# MPBoard_L3_Relay2_ext.net
KiCad netlist of a schematic drawn in Altium Designer
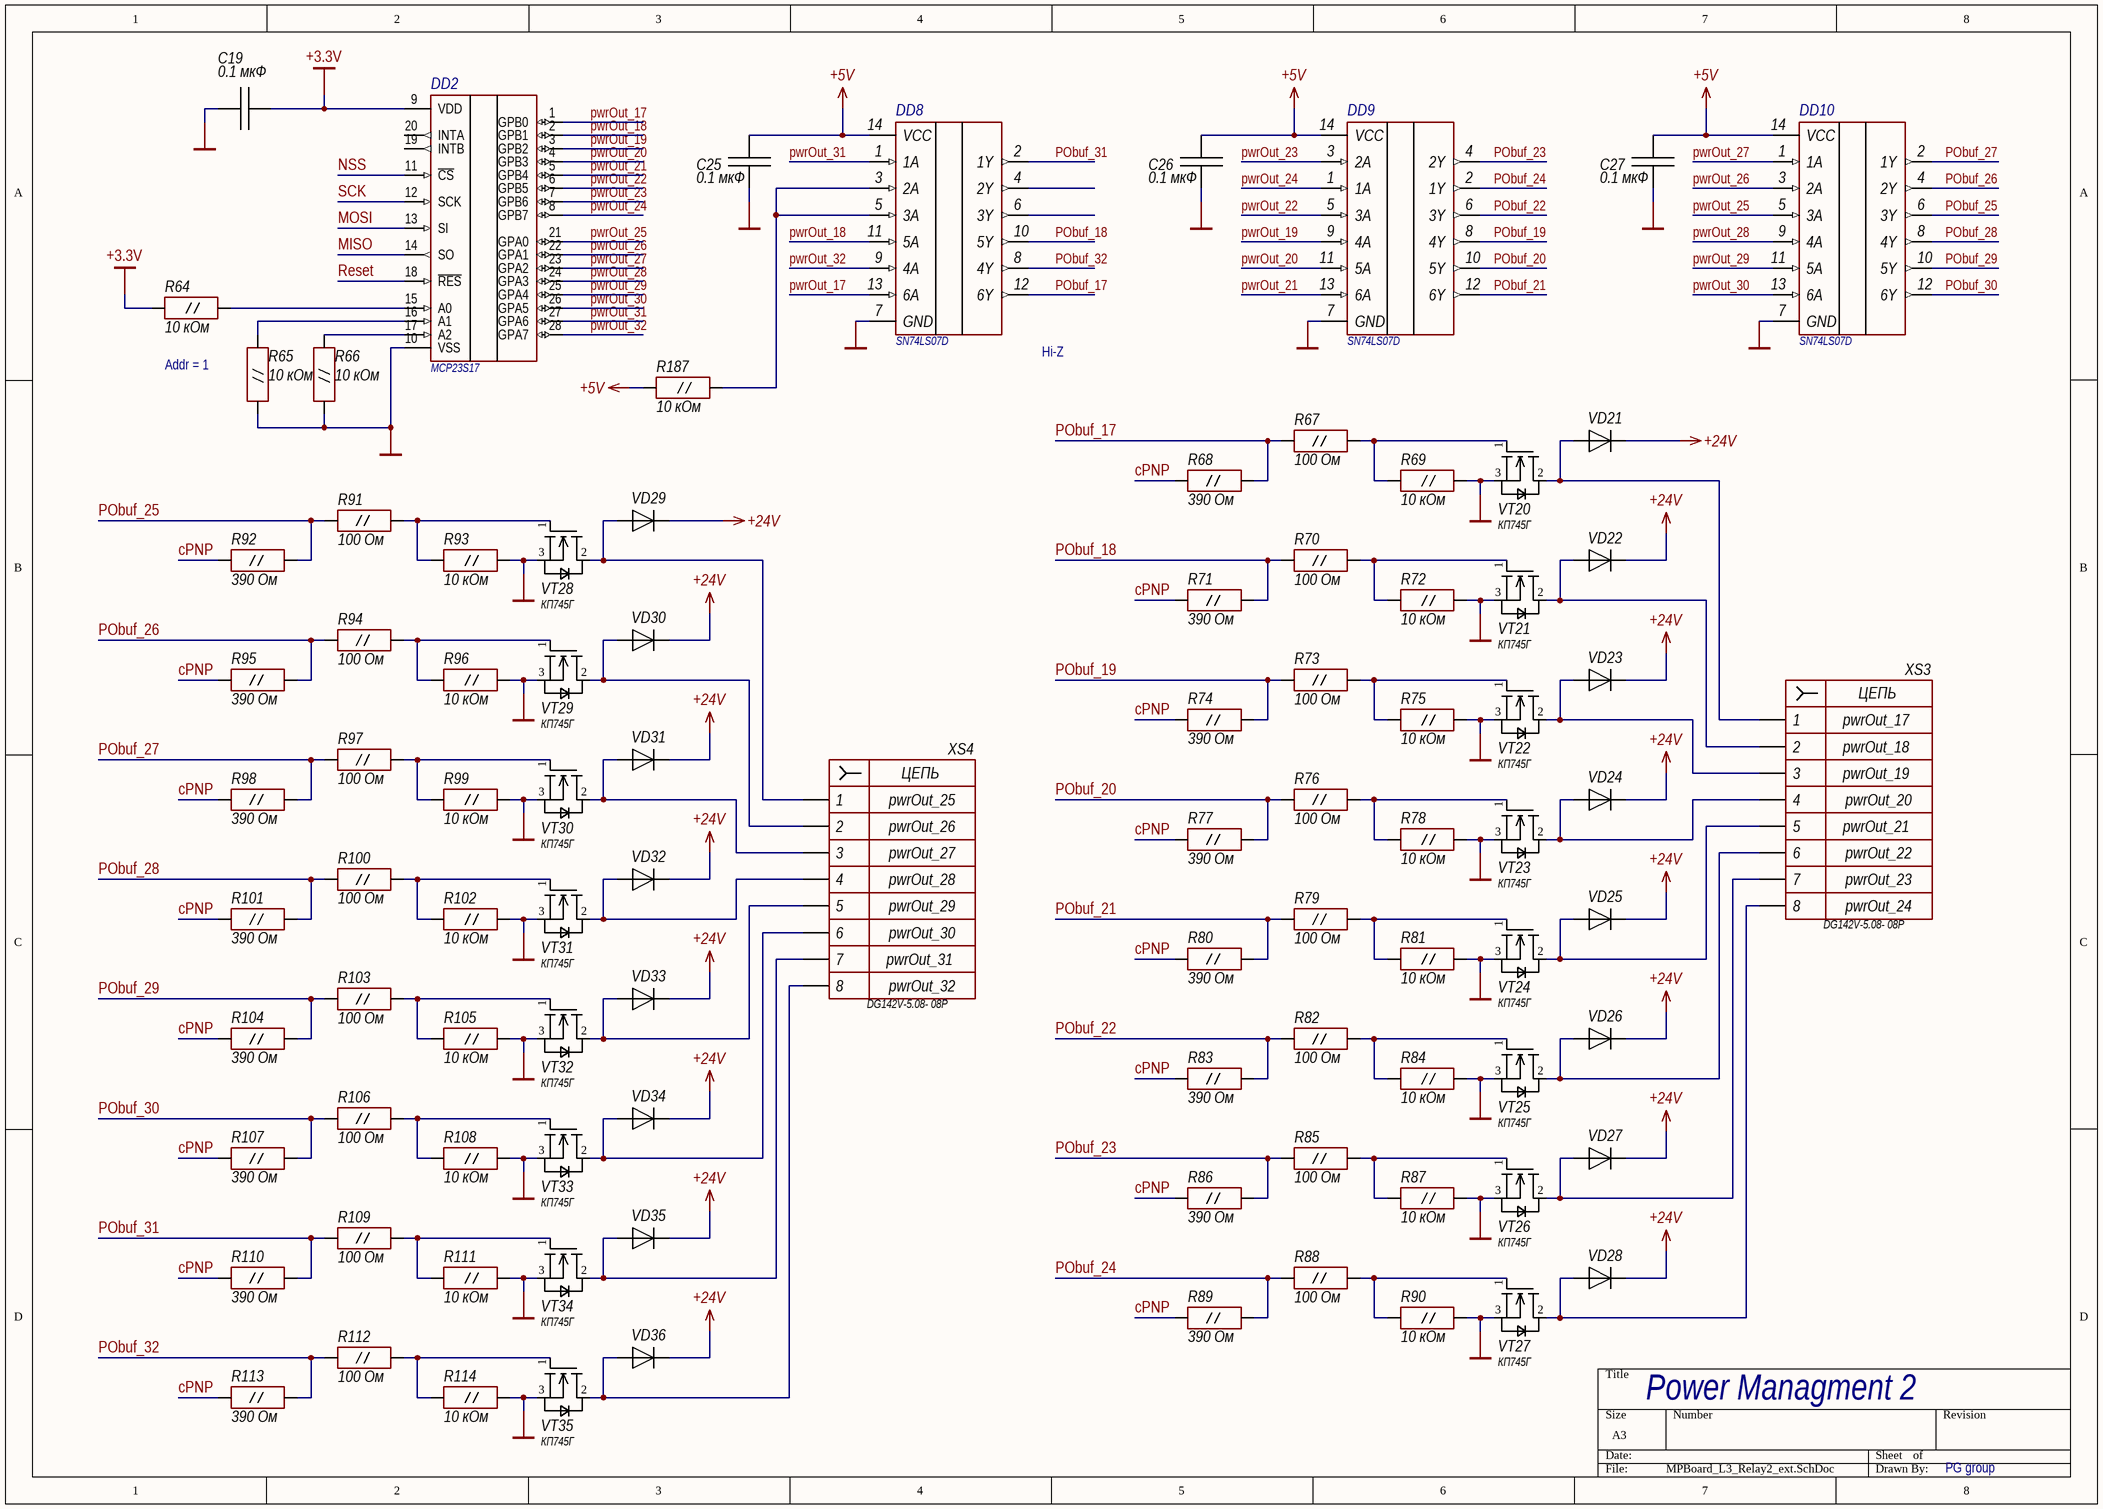
[diagram p0: MPBoard_L3_Relay2_ext.SchDoc]

(export (version "E")
  (design (tool "Eeschema 10.0.6"))
  (components
    (comp (ref "C19")
      (value "0.1 мкФ")
      (footprint "CAP-0603")
      (description "Конденсатор")
      (fields (field (name "MF") "KEMET") (field (name "TOLERANCE") "± 10 %"))
      (libsource (lib "MainBoard") (part "C"))
    )
    (comp (ref "C25")
      (value "0.1 мкФ")
      (footprint "CAP-0603")
      (description "Конденсатор")
      (fields (field (name "MF") "KEMET") (field (name "TOLERANCE") "± 10 %"))
      (libsource (lib "MainBoard") (part "C"))
    )
    (comp (ref "C26")
      (value "0.1 мкФ")
      (footprint "CAP-0603")
      (description "Конденсатор")
      (fields (field (name "MF") "KEMET") (field (name "TOLERANCE") "± 10 %"))
      (libsource (lib "MainBoard") (part "C"))
    )
    (comp (ref "C27")
      (value "0.1 мкФ")
      (footprint "CAP-0603")
      (description "Конденсатор")
      (fields (field (name "MF") "KEMET") (field (name "TOLERANCE") "± 10 %"))
      (libsource (lib "MainBoard") (part "C"))
    )
    (comp (ref "DD2")
      (value "MCP23S17")
      (footprint "SOIC-28")
      (description "I/O Expander 16 SPI")
      (fields (field (name "MF") "Microchip"))
      (libsource (lib "MPBoard") (part "DD_MCP23S17"))
    )
    (comp (ref "DD8")
      (value "SN74LS07D")
      (footprint "SOIC-14")
      (description "6-ch, 4.75_5.25V bipolar buffers with OC outputs")
      (fields (field (name "MF") "Texas Instruments"))
      (libsource (lib "MPBoard") (part "DD_SN74LS07D"))
    )
    (comp (ref "DD9")
      (value "SN74LS07D")
      (footprint "SOIC-14")
      (description "6-ch, 4.75_5.25V bipolar buffers with OC outputs")
      (fields (field (name "MF") "Texas Instruments"))
      (libsource (lib "") (part "DD_SN74LS07D_1"))
    )
    (comp (ref "DD10")
      (value "SN74LS07D")
      (footprint "SOIC-14")
      (description "6-ch, 4.75_5.25V bipolar buffers with OC outputs")
      (fields (field (name "MF") "Texas Instruments"))
      (libsource (lib "") (part "DD_SN74LS07D_2"))
    )
    (comp (ref "R64")
      (value "10 кОм")
      (footprint "RES-0603")
      (description "Резистор 0.1 W")
      (fields (field (name "MF") "Vishay") (field (name "TOLERANCE") "± 1 %"))
      (libsource (lib "") (part "R_0.125W_1"))
    )
    (comp (ref "R65")
      (value "10 кОм")
      (footprint "RES-0603")
      (description "Резистор 0.1 W")
      (fields (field (name "MF") "Vishay") (field (name "TOLERANCE") "± 1 %"))
      (libsource (lib "") (part "R_0.125W_2"))
    )
    (comp (ref "R66")
      (value "10 кОм")
      (footprint "RES-0603")
      (description "Резистор 0.1 W")
      (fields (field (name "MF") "Vishay") (field (name "TOLERANCE") "± 1 %"))
      (libsource (lib "") (part "R_0.125W_2"))
    )
    (comp (ref "R67")
      (value "100 Ом")
      (footprint "RES-0805")
      (description "Резистор 0.125 W")
      (fields (field (name "MF") "Vishay") (field (name "TOLERANCE") "± 1 %"))
      (libsource (lib "MainBoard") (part "R_0.125W"))
    )
    (comp (ref "R68")
      (value "390 Ом")
      (footprint "RES-0805")
      (description "Резистор 0.125 W")
      (fields (field (name "MF") "Vishay") (field (name "TOLERANCE") "± 1 %"))
      (libsource (lib "MainBoard") (part "R_0.125W"))
    )
    (comp (ref "R69")
      (value "10 кОм")
      (footprint "RES-0805")
      (description "Резистор 0.125 W")
      (fields (field (name "MF") "Vishay") (field (name "TOLERANCE") "± 1 %"))
      (libsource (lib "") (part "R_0.125W_1"))
    )
    (comp (ref "R70")
      (value "100 Ом")
      (footprint "RES-0805")
      (description "Резистор 0.125 W")
      (fields (field (name "MF") "Vishay") (field (name "TOLERANCE") "± 1 %"))
      (libsource (lib "MainBoard") (part "R_0.125W"))
    )
    (comp (ref "R71")
      (value "390 Ом")
      (footprint "RES-0805")
      (description "Резистор 0.125 W")
      (fields (field (name "MF") "Vishay") (field (name "TOLERANCE") "± 1 %"))
      (libsource (lib "MainBoard") (part "R_0.125W"))
    )
    (comp (ref "R72")
      (value "10 кОм")
      (footprint "RES-0805")
      (description "Резистор 0.125 W")
      (fields (field (name "MF") "Vishay") (field (name "TOLERANCE") "± 1 %"))
      (libsource (lib "") (part "R_0.125W_1"))
    )
    (comp (ref "R73")
      (value "100 Ом")
      (footprint "RES-0805")
      (description "Резистор 0.125 W")
      (fields (field (name "MF") "Vishay") (field (name "TOLERANCE") "± 1 %"))
      (libsource (lib "MainBoard") (part "R_0.125W"))
    )
    (comp (ref "R74")
      (value "390 Ом")
      (footprint "RES-0805")
      (description "Резистор 0.125 W")
      (fields (field (name "MF") "Vishay") (field (name "TOLERANCE") "± 1 %"))
      (libsource (lib "MainBoard") (part "R_0.125W"))
    )
    (comp (ref "R75")
      (value "10 кОм")
      (footprint "RES-0805")
      (description "Резистор 0.125 W")
      (fields (field (name "MF") "Vishay") (field (name "TOLERANCE") "± 1 %"))
      (libsource (lib "") (part "R_0.125W_1"))
    )
    (comp (ref "R76")
      (value "100 Ом")
      (footprint "RES-0805")
      (description "Резистор 0.125 W")
      (fields (field (name "MF") "Vishay") (field (name "TOLERANCE") "± 1 %"))
      (libsource (lib "MainBoard") (part "R_0.125W"))
    )
    (comp (ref "R77")
      (value "390 Ом")
      (footprint "RES-0805")
      (description "Резистор 0.125 W")
      (fields (field (name "MF") "Vishay") (field (name "TOLERANCE") "± 1 %"))
      (libsource (lib "MainBoard") (part "R_0.125W"))
    )
    (comp (ref "R78")
      (value "10 кОм")
      (footprint "RES-0805")
      (description "Резистор 0.125 W")
      (fields (field (name "MF") "Vishay") (field (name "TOLERANCE") "± 1 %"))
      (libsource (lib "") (part "R_0.125W_1"))
    )
    (comp (ref "R79")
      (value "100 Ом")
      (footprint "RES-0805")
      (description "Резистор 0.125 W")
      (fields (field (name "MF") "Vishay") (field (name "TOLERANCE") "± 1 %"))
      (libsource (lib "MainBoard") (part "R_0.125W"))
    )
    (comp (ref "R80")
      (value "390 Ом")
      (footprint "RES-0805")
      (description "Резистор 0.125 W")
      (fields (field (name "MF") "Vishay") (field (name "TOLERANCE") "± 1 %"))
      (libsource (lib "MainBoard") (part "R_0.125W"))
    )
    (comp (ref "R81")
      (value "10 кОм")
      (footprint "RES-0805")
      (description "Резистор 0.125 W")
      (fields (field (name "MF") "Vishay") (field (name "TOLERANCE") "± 1 %"))
      (libsource (lib "") (part "R_0.125W_1"))
    )
    (comp (ref "R82")
      (value "100 Ом")
      (footprint "RES-0805")
      (description "Резистор 0.125 W")
      (fields (field (name "MF") "Vishay") (field (name "TOLERANCE") "± 1 %"))
      (libsource (lib "MainBoard") (part "R_0.125W"))
    )
    (comp (ref "R83")
      (value "390 Ом")
      (footprint "RES-0805")
      (description "Резистор 0.125 W")
      (fields (field (name "MF") "Vishay") (field (name "TOLERANCE") "± 1 %"))
      (libsource (lib "MainBoard") (part "R_0.125W"))
    )
    (comp (ref "R84")
      (value "10 кОм")
      (footprint "RES-0805")
      (description "Резистор 0.125 W")
      (fields (field (name "MF") "Vishay") (field (name "TOLERANCE") "± 1 %"))
      (libsource (lib "") (part "R_0.125W_1"))
    )
    (comp (ref "R85")
      (value "100 Ом")
      (footprint "RES-0805")
      (description "Резистор 0.125 W")
      (fields (field (name "MF") "Vishay") (field (name "TOLERANCE") "± 1 %"))
      (libsource (lib "MainBoard") (part "R_0.125W"))
    )
    (comp (ref "R86")
      (value "390 Ом")
      (footprint "RES-0805")
      (description "Резистор 0.125 W")
      (fields (field (name "MF") "Vishay") (field (name "TOLERANCE") "± 1 %"))
      (libsource (lib "MainBoard") (part "R_0.125W"))
    )
    (comp (ref "R87")
      (value "10 кОм")
      (footprint "RES-0805")
      (description "Резистор 0.125 W")
      (fields (field (name "MF") "Vishay") (field (name "TOLERANCE") "± 1 %"))
      (libsource (lib "") (part "R_0.125W_1"))
    )
    (comp (ref "R88")
      (value "100 Ом")
      (footprint "RES-0805")
      (description "Резистор 0.125 W")
      (fields (field (name "MF") "Vishay") (field (name "TOLERANCE") "± 1 %"))
      (libsource (lib "MainBoard") (part "R_0.125W"))
    )
    (comp (ref "R89")
      (value "390 Ом")
      (footprint "RES-0805")
      (description "Резистор 0.125 W")
      (fields (field (name "MF") "Vishay") (field (name "TOLERANCE") "± 1 %"))
      (libsource (lib "MainBoard") (part "R_0.125W"))
    )
    (comp (ref "R90")
      (value "10 кОм")
      (footprint "RES-0805")
      (description "Резистор 0.125 W")
      (fields (field (name "MF") "Vishay") (field (name "TOLERANCE") "± 1 %"))
      (libsource (lib "") (part "R_0.125W_1"))
    )
    (comp (ref "R91")
      (value "100 Ом")
      (footprint "RES-0805")
      (description "Резистор 0.125 W")
      (fields (field (name "MF") "Vishay") (field (name "TOLERANCE") "± 1 %"))
      (libsource (lib "MainBoard") (part "R_0.125W"))
    )
    (comp (ref "R92")
      (value "390 Ом")
      (footprint "RES-0805")
      (description "Резистор 0.125 W")
      (fields (field (name "MF") "Vishay") (field (name "TOLERANCE") "± 1 %"))
      (libsource (lib "MainBoard") (part "R_0.125W"))
    )
    (comp (ref "R93")
      (value "10 кОм")
      (footprint "RES-0805")
      (description "Резистор 0.125 W")
      (fields (field (name "MF") "Vishay") (field (name "TOLERANCE") "± 1 %"))
      (libsource (lib "") (part "R_0.125W_1"))
    )
    (comp (ref "R94")
      (value "100 Ом")
      (footprint "RES-0805")
      (description "Резистор 0.125 W")
      (fields (field (name "MF") "Vishay") (field (name "TOLERANCE") "± 1 %"))
      (libsource (lib "MainBoard") (part "R_0.125W"))
    )
    (comp (ref "R95")
      (value "390 Ом")
      (footprint "RES-0805")
      (description "Резистор 0.125 W")
      (fields (field (name "MF") "Vishay") (field (name "TOLERANCE") "± 1 %"))
      (libsource (lib "MainBoard") (part "R_0.125W"))
    )
    (comp (ref "R96")
      (value "10 кОм")
      (footprint "RES-0805")
      (description "Резистор 0.125 W")
      (fields (field (name "MF") "Vishay") (field (name "TOLERANCE") "± 1 %"))
      (libsource (lib "") (part "R_0.125W_1"))
    )
    (comp (ref "R97")
      (value "100 Ом")
      (footprint "RES-0805")
      (description "Резистор 0.125 W")
      (fields (field (name "MF") "Vishay") (field (name "TOLERANCE") "± 1 %"))
      (libsource (lib "MainBoard") (part "R_0.125W"))
    )
    (comp (ref "R98")
      (value "390 Ом")
      (footprint "RES-0805")
      (description "Резистор 0.125 W")
      (fields (field (name "MF") "Vishay") (field (name "TOLERANCE") "± 1 %"))
      (libsource (lib "MainBoard") (part "R_0.125W"))
    )
    (comp (ref "R99")
      (value "10 кОм")
      (footprint "RES-0805")
      (description "Резистор 0.125 W")
      (fields (field (name "MF") "Vishay") (field (name "TOLERANCE") "± 1 %"))
      (libsource (lib "") (part "R_0.125W_1"))
    )
    (comp (ref "R100")
      (value "100 Ом")
      (footprint "RES-0805")
      (description "Резистор 0.125 W")
      (fields (field (name "MF") "Vishay") (field (name "TOLERANCE") "± 1 %"))
      (libsource (lib "MainBoard") (part "R_0.125W"))
    )
    (comp (ref "R101")
      (value "390 Ом")
      (footprint "RES-0805")
      (description "Резистор 0.125 W")
      (fields (field (name "MF") "Vishay") (field (name "TOLERANCE") "± 1 %"))
      (libsource (lib "MainBoard") (part "R_0.125W"))
    )
    (comp (ref "R102")
      (value "10 кОм")
      (footprint "RES-0805")
      (description "Резистор 0.125 W")
      (fields (field (name "MF") "Vishay") (field (name "TOLERANCE") "± 1 %"))
      (libsource (lib "") (part "R_0.125W_1"))
    )
    (comp (ref "R103")
      (value "100 Ом")
      (footprint "RES-0805")
      (description "Резистор 0.125 W")
      (fields (field (name "MF") "Vishay") (field (name "TOLERANCE") "± 1 %"))
      (libsource (lib "MainBoard") (part "R_0.125W"))
    )
    (comp (ref "R104")
      (value "390 Ом")
      (footprint "RES-0805")
      (description "Резистор 0.125 W")
      (fields (field (name "MF") "Vishay") (field (name "TOLERANCE") "± 1 %"))
      (libsource (lib "MainBoard") (part "R_0.125W"))
    )
    (comp (ref "R105")
      (value "10 кОм")
      (footprint "RES-0805")
      (description "Резистор 0.125 W")
      (fields (field (name "MF") "Vishay") (field (name "TOLERANCE") "± 1 %"))
      (libsource (lib "") (part "R_0.125W_1"))
    )
    (comp (ref "R106")
      (value "100 Ом")
      (footprint "RES-0805")
      (description "Резистор 0.125 W")
      (fields (field (name "MF") "Vishay") (field (name "TOLERANCE") "± 1 %"))
      (libsource (lib "MainBoard") (part "R_0.125W"))
    )
    (comp (ref "R107")
      (value "390 Ом")
      (footprint "RES-0805")
      (description "Резистор 0.125 W")
      (fields (field (name "MF") "Vishay") (field (name "TOLERANCE") "± 1 %"))
      (libsource (lib "MainBoard") (part "R_0.125W"))
    )
    (comp (ref "R108")
      (value "10 кОм")
      (footprint "RES-0805")
      (description "Резистор 0.125 W")
      (fields (field (name "MF") "Vishay") (field (name "TOLERANCE") "± 1 %"))
      (libsource (lib "") (part "R_0.125W_1"))
    )
    (comp (ref "R109")
      (value "100 Ом")
      (footprint "RES-0805")
      (description "Резистор 0.125 W")
      (fields (field (name "MF") "Vishay") (field (name "TOLERANCE") "± 1 %"))
      (libsource (lib "MainBoard") (part "R_0.125W"))
    )
    (comp (ref "R110")
      (value "390 Ом")
      (footprint "RES-0805")
      (description "Резистор 0.125 W")
      (fields (field (name "MF") "Vishay") (field (name "TOLERANCE") "± 1 %"))
      (libsource (lib "MainBoard") (part "R_0.125W"))
    )
    (comp (ref "R111")
      (value "10 кОм")
      (footprint "RES-0805")
      (description "Резистор 0.125 W")
      (fields (field (name "MF") "Vishay") (field (name "TOLERANCE") "± 1 %"))
      (libsource (lib "") (part "R_0.125W_1"))
    )
    (comp (ref "R112")
      (value "100 Ом")
      (footprint "RES-0805")
      (description "Резистор 0.125 W")
      (fields (field (name "MF") "Vishay") (field (name "TOLERANCE") "± 1 %"))
      (libsource (lib "MainBoard") (part "R_0.125W"))
    )
    (comp (ref "R113")
      (value "390 Ом")
      (footprint "RES-0805")
      (description "Резистор 0.125 W")
      (fields (field (name "MF") "Vishay") (field (name "TOLERANCE") "± 1 %"))
      (libsource (lib "MainBoard") (part "R_0.125W"))
    )
    (comp (ref "R114")
      (value "10 кОм")
      (footprint "RES-0805")
      (description "Резистор 0.125 W")
      (fields (field (name "MF") "Vishay") (field (name "TOLERANCE") "± 1 %"))
      (libsource (lib "") (part "R_0.125W_1"))
    )
    (comp (ref "R187")
      (value "10 кОм")
      (footprint "RES-0603")
      (description "Резистор 0.1 W")
      (fields (field (name "MF") "Vishay") (field (name "TOLERANCE") "± 1 %"))
      (libsource (lib "") (part "R_0.125W_1"))
    )
    (comp (ref "VD21")
      (value "HER108")
      (footprint "DIOD-MILS-400")
      (description "Диод Выпрямительный")
      (fields (field (name "MF") "Taiwan Semiconductor") (field (name "MFPARTNUM") "HER108G"))
      (libsource (lib "MainBoard") (part "VD"))
    )
    (comp (ref "VD22")
      (value "HER108")
      (footprint "DIOD-MILS-400")
      (description "Диод Выпрямительный")
      (fields (field (name "MF") "Taiwan Semiconductor") (field (name "MFPARTNUM") "HER108G"))
      (libsource (lib "MainBoard") (part "VD"))
    )
    (comp (ref "VD23")
      (value "HER108")
      (footprint "DIOD-MILS-400")
      (description "Диод Выпрямительный")
      (fields (field (name "MF") "Taiwan Semiconductor") (field (name "MFPARTNUM") "HER108G"))
      (libsource (lib "MainBoard") (part "VD"))
    )
    (comp (ref "VD24")
      (value "HER108")
      (footprint "DIOD-MILS-400")
      (description "Диод Выпрямительный")
      (fields (field (name "MF") "Taiwan Semiconductor") (field (name "MFPARTNUM") "HER108G"))
      (libsource (lib "MainBoard") (part "VD"))
    )
    (comp (ref "VD25")
      (value "HER108")
      (footprint "DIOD-MILS-400")
      (description "Диод Выпрямительный")
      (fields (field (name "MF") "Taiwan Semiconductor") (field (name "MFPARTNUM") "HER108G"))
      (libsource (lib "MainBoard") (part "VD"))
    )
    (comp (ref "VD26")
      (value "HER108")
      (footprint "DIOD-MILS-400")
      (description "Диод Выпрямительный")
      (fields (field (name "MF") "Taiwan Semiconductor") (field (name "MFPARTNUM") "HER108G"))
      (libsource (lib "MainBoard") (part "VD"))
    )
    (comp (ref "VD27")
      (value "HER108")
      (footprint "DIOD-MILS-400")
      (description "Диод Выпрямительный")
      (fields (field (name "MF") "Taiwan Semiconductor") (field (name "MFPARTNUM") "HER108G"))
      (libsource (lib "MainBoard") (part "VD"))
    )
    (comp (ref "VD28")
      (value "HER108")
      (footprint "DIOD-MILS-400")
      (description "Диод Выпрямительный")
      (fields (field (name "MF") "Taiwan Semiconductor") (field (name "MFPARTNUM") "HER108G"))
      (libsource (lib "MainBoard") (part "VD"))
    )
    (comp (ref "VD29")
      (value "HER108")
      (footprint "DIOD-MILS-400")
      (description "Диод Выпрямительный")
      (fields (field (name "MF") "Taiwan Semiconductor") (field (name "MFPARTNUM") "HER108G"))
      (libsource (lib "MainBoard") (part "VD"))
    )
    (comp (ref "VD30")
      (value "HER108")
      (footprint "DIOD-MILS-400")
      (description "Диод Выпрямительный")
      (fields (field (name "MF") "Taiwan Semiconductor") (field (name "MFPARTNUM") "HER108G"))
      (libsource (lib "MainBoard") (part "VD"))
    )
    (comp (ref "VD31")
      (value "HER108")
      (footprint "DIOD-MILS-400")
      (description "Диод Выпрямительный")
      (fields (field (name "MF") "Taiwan Semiconductor") (field (name "MFPARTNUM") "HER108G"))
      (libsource (lib "MainBoard") (part "VD"))
    )
    (comp (ref "VD32")
      (value "HER108")
      (footprint "DIOD-MILS-400")
      (description "Диод Выпрямительный")
      (fields (field (name "MF") "Taiwan Semiconductor") (field (name "MFPARTNUM") "HER108G"))
      (libsource (lib "MainBoard") (part "VD"))
    )
    (comp (ref "VD33")
      (value "HER108")
      (footprint "DIOD-MILS-400")
      (description "Диод Выпрямительный")
      (fields (field (name "MF") "Taiwan Semiconductor") (field (name "MFPARTNUM") "HER108G"))
      (libsource (lib "MainBoard") (part "VD"))
    )
    (comp (ref "VD34")
      (value "HER108")
      (footprint "DIOD-MILS-400")
      (description "Диод Выпрямительный")
      (fields (field (name "MF") "Taiwan Semiconductor") (field (name "MFPARTNUM") "HER108G"))
      (libsource (lib "MainBoard") (part "VD"))
    )
    (comp (ref "VD35")
      (value "HER108")
      (footprint "DIOD-MILS-400")
      (description "Диод Выпрямительный")
      (fields (field (name "MF") "Taiwan Semiconductor") (field (name "MFPARTNUM") "HER108G"))
      (libsource (lib "MainBoard") (part "VD"))
    )
    (comp (ref "VD36")
      (value "HER108")
      (footprint "DIOD-MILS-400")
      (description "Диод Выпрямительный")
      (fields (field (name "MF") "Taiwan Semiconductor") (field (name "MFPARTNUM") "HER108G"))
      (libsource (lib "MainBoard") (part "VD"))
    )
    (comp (ref "VT20")
      (value "КП745Г")
      (footprint "TO220S inline")
      (description "MOSFET")
      (fields (field (name "MF") "Интеграл") (field (name "VOLTAGE") "100 В"))
      (libsource (lib "MPBoard") (part "VT_N-MOSFET"))
    )
    (comp (ref "VT21")
      (value "КП745Г")
      (footprint "TO220S inline")
      (description "MOSFET")
      (fields (field (name "MF") "Интеграл") (field (name "VOLTAGE") "100 В"))
      (libsource (lib "MPBoard") (part "VT_N-MOSFET"))
    )
    (comp (ref "VT22")
      (value "КП745Г")
      (footprint "TO220S inline")
      (description "MOSFET")
      (fields (field (name "MF") "Интеграл") (field (name "VOLTAGE") "100 В"))
      (libsource (lib "MPBoard") (part "VT_N-MOSFET"))
    )
    (comp (ref "VT23")
      (value "КП745Г")
      (footprint "TO220S inline")
      (description "MOSFET")
      (fields (field (name "MF") "Интеграл") (field (name "VOLTAGE") "100 В"))
      (libsource (lib "MPBoard") (part "VT_N-MOSFET"))
    )
    (comp (ref "VT24")
      (value "КП745Г")
      (footprint "TO220S inline")
      (description "MOSFET")
      (fields (field (name "MF") "Интеграл") (field (name "VOLTAGE") "100 В"))
      (libsource (lib "MPBoard") (part "VT_N-MOSFET"))
    )
    (comp (ref "VT25")
      (value "КП745Г")
      (footprint "TO220S inline")
      (description "MOSFET")
      (fields (field (name "MF") "Интеграл") (field (name "VOLTAGE") "100 В"))
      (libsource (lib "MPBoard") (part "VT_N-MOSFET"))
    )
    (comp (ref "VT26")
      (value "КП745Г")
      (footprint "TO220S inline")
      (description "MOSFET")
      (fields (field (name "MF") "Интеграл") (field (name "VOLTAGE") "100 В"))
      (libsource (lib "MPBoard") (part "VT_N-MOSFET"))
    )
    (comp (ref "VT27")
      (value "КП745Г")
      (footprint "TO220S inline")
      (description "MOSFET")
      (fields (field (name "MF") "Интеграл") (field (name "VOLTAGE") "100 В"))
      (libsource (lib "MPBoard") (part "VT_N-MOSFET"))
    )
    (comp (ref "VT28")
      (value "КП745Г")
      (footprint "TO220S inline")
      (description "MOSFET")
      (fields (field (name "MF") "Интеграл") (field (name "VOLTAGE") "100 В"))
      (libsource (lib "MPBoard") (part "VT_N-MOSFET"))
    )
    (comp (ref "VT29")
      (value "КП745Г")
      (footprint "TO220S inline")
      (description "MOSFET")
      (fields (field (name "MF") "Интеграл") (field (name "VOLTAGE") "100 В"))
      (libsource (lib "MPBoard") (part "VT_N-MOSFET"))
    )
    (comp (ref "VT30")
      (value "КП745Г")
      (footprint "TO220S inline")
      (description "MOSFET")
      (fields (field (name "MF") "Интеграл") (field (name "VOLTAGE") "100 В"))
      (libsource (lib "MPBoard") (part "VT_N-MOSFET"))
    )
    (comp (ref "VT31")
      (value "КП745Г")
      (footprint "TO220S inline")
      (description "MOSFET")
      (fields (field (name "MF") "Интеграл") (field (name "VOLTAGE") "100 В"))
      (libsource (lib "MPBoard") (part "VT_N-MOSFET"))
    )
    (comp (ref "VT32")
      (value "КП745Г")
      (footprint "TO220S inline")
      (description "MOSFET")
      (fields (field (name "MF") "Интеграл") (field (name "VOLTAGE") "100 В"))
      (libsource (lib "MPBoard") (part "VT_N-MOSFET"))
    )
    (comp (ref "VT33")
      (value "КП745Г")
      (footprint "TO220S inline")
      (description "MOSFET")
      (fields (field (name "MF") "Интеграл") (field (name "VOLTAGE") "100 В"))
      (libsource (lib "MPBoard") (part "VT_N-MOSFET"))
    )
    (comp (ref "VT34")
      (value "КП745Г")
      (footprint "TO220S inline")
      (description "MOSFET")
      (fields (field (name "MF") "Интеграл") (field (name "VOLTAGE") "100 В"))
      (libsource (lib "MPBoard") (part "VT_N-MOSFET"))
    )
    (comp (ref "VT35")
      (value "КП745Г")
      (footprint "TO220S inline")
      (description "MOSFET")
      (fields (field (name "MF") "Интеграл") (field (name "VOLTAGE") "100 В"))
      (libsource (lib "MPBoard") (part "VT_N-MOSFET"))
    )
    (comp (ref "XS3")
      (value "DG142V-5.08- 08P")
      (footprint "DG142V-5.08-08")
      (description "розетка 8 контактов")
      (fields
        (field (name "MF") "Degson Electronics")
        (field (name "MFPARTNUM") "DG142V-5.08- 08P-14-00A(H)")
        (field (name "NET6") "pwrOut_22")
        (field (name "NET5") "pwrOut_21")
        (field (name "NET1") "pwrOut_17")
        (field (name "NET2") "pwrOut_18")
        (field (name "NET3") "pwrOut_19")
        (field (name "NET4") "pwrOut_20")
        (field (name "NET7") "pwrOut_23")
        (field (name "NET8") "pwrOut_24")
      )
      (libsource (lib "MPBoard") (part "XS8"))
    )
    (comp (ref "XS4")
      (value "DG142V-5.08- 08P")
      (footprint "DG142V-5.08-08")
      (description "розетка 8 контактов")
      (fields
        (field (name "MF") "Degson Electronics")
        (field (name "MFPARTNUM") "DG142V-5.08- 08P-14-00A(H)")
        (field (name "NET6") "pwrOut_30")
        (field (name "NET5") "pwrOut_29")
        (field (name "NET1") "pwrOut_25")
        (field (name "NET2") "pwrOut_26")
        (field (name "NET3") "pwrOut_27")
        (field (name "NET4") "pwrOut_28")
        (field (name "NET7") "pwrOut_31")
        (field (name "NET8") "pwrOut_32")
      )
      (libsource (lib "MPBoard") (part "XS8"))
    )
  )
  (nets
    (net (code "1") (name "+3.3V") (class "Default")
      (node (ref "C19") (pin "2") (pinfunction "2_2") (pintype "passive"))
      (node (ref "DD2") (pin "9") (pinfunction "VDD_9") (pintype "power_in"))
      (node (ref "R64") (pin "2") (pinfunction "2_2") (pintype "passive"))
    )
    (net (code "2") (name "+5V") (class "Default")
      (node (ref "C25") (pin "2") (pinfunction "2_2") (pintype "passive"))
      (node (ref "C26") (pin "2") (pinfunction "2_2") (pintype "passive"))
      (node (ref "C27") (pin "2") (pinfunction "2_2") (pintype "passive"))
      (node (ref "DD10") (pin "14") (pinfunction "VCC_14") (pintype "power_in"))
      (node (ref "DD8") (pin "14") (pinfunction "VCC_14") (pintype "power_in"))
      (node (ref "DD9") (pin "14") (pinfunction "VCC_14") (pintype "power_in"))
      (node (ref "R187") (pin "2") (pinfunction "2_2") (pintype "passive"))
    )
    (net (code "3") (name "+24V") (class "Default")
      (node (ref "VD21") (pin "2") (pinfunction "2_2") (pintype "passive"))
      (node (ref "VD22") (pin "2") (pinfunction "2_2") (pintype "passive"))
      (node (ref "VD23") (pin "2") (pinfunction "2_2") (pintype "passive"))
      (node (ref "VD24") (pin "2") (pinfunction "2_2") (pintype "passive"))
      (node (ref "VD25") (pin "2") (pinfunction "2_2") (pintype "passive"))
      (node (ref "VD26") (pin "2") (pinfunction "2_2") (pintype "passive"))
      (node (ref "VD27") (pin "2") (pinfunction "2_2") (pintype "passive"))
      (node (ref "VD28") (pin "2") (pinfunction "2_2") (pintype "passive"))
      (node (ref "VD29") (pin "2") (pinfunction "2_2") (pintype "passive"))
      (node (ref "VD30") (pin "2") (pinfunction "2_2") (pintype "passive"))
      (node (ref "VD31") (pin "2") (pinfunction "2_2") (pintype "passive"))
      (node (ref "VD32") (pin "2") (pinfunction "2_2") (pintype "passive"))
      (node (ref "VD33") (pin "2") (pinfunction "2_2") (pintype "passive"))
      (node (ref "VD34") (pin "2") (pinfunction "2_2") (pintype "passive"))
      (node (ref "VD35") (pin "2") (pinfunction "2_2") (pintype "passive"))
      (node (ref "VD36") (pin "2") (pinfunction "2_2") (pintype "passive"))
    )
    (net (code "4") (name "/MISO") (class "Default")
      (node (ref "DD2") (pin "14") (pinfunction "SO_14") (pintype "output"))
    )
    (net (code "5") (name "/MOSI") (class "Default")
      (node (ref "DD2") (pin "13") (pinfunction "SI_13") (pintype "input"))
    )
    (net (code "6") (name "/NSS") (class "Default")
      (node (ref "DD2") (pin "11") (pinfunction "~{CS}_11") (pintype "input"))
    )
    (net (code "7") (name "/PObuf_17") (class "Default")
      (node (ref "DD8") (pin "12") (pinfunction "6Y_12") (pintype "output"))
      (node (ref "R67") (pin "1") (pinfunction "1_1") (pintype "passive"))
      (node (ref "R68") (pin "2") (pinfunction "2_2") (pintype "passive"))
    )
    (net (code "8") (name "/PObuf_18") (class "Default")
      (node (ref "DD8") (pin "10") (pinfunction "5Y_10") (pintype "output"))
      (node (ref "R70") (pin "1") (pinfunction "1_1") (pintype "passive"))
      (node (ref "R71") (pin "2") (pinfunction "2_2") (pintype "passive"))
    )
    (net (code "9") (name "/PObuf_19") (class "Default")
      (node (ref "DD9") (pin "8") (pinfunction "4Y_8") (pintype "output"))
      (node (ref "R73") (pin "1") (pinfunction "1_1") (pintype "passive"))
      (node (ref "R74") (pin "2") (pinfunction "2_2") (pintype "passive"))
    )
    (net (code "10") (name "/PObuf_20") (class "Default")
      (node (ref "DD9") (pin "10") (pinfunction "5Y_10") (pintype "output"))
      (node (ref "R76") (pin "1") (pinfunction "1_1") (pintype "passive"))
      (node (ref "R77") (pin "2") (pinfunction "2_2") (pintype "passive"))
    )
    (net (code "11") (name "/PObuf_21") (class "Default")
      (node (ref "DD9") (pin "12") (pinfunction "6Y_12") (pintype "output"))
      (node (ref "R79") (pin "1") (pinfunction "1_1") (pintype "passive"))
      (node (ref "R80") (pin "2") (pinfunction "2_2") (pintype "passive"))
    )
    (net (code "12") (name "/PObuf_22") (class "Default")
      (node (ref "DD9") (pin "6") (pinfunction "3Y_6") (pintype "output"))
      (node (ref "R82") (pin "1") (pinfunction "1_1") (pintype "passive"))
      (node (ref "R83") (pin "2") (pinfunction "2_2") (pintype "passive"))
    )
    (net (code "13") (name "/PObuf_23") (class "Default")
      (node (ref "DD9") (pin "4") (pinfunction "2Y_4") (pintype "output"))
      (node (ref "R85") (pin "1") (pinfunction "1_1") (pintype "passive"))
      (node (ref "R86") (pin "2") (pinfunction "2_2") (pintype "passive"))
    )
    (net (code "14") (name "/PObuf_24") (class "Default")
      (node (ref "DD9") (pin "2") (pinfunction "1Y_2") (pintype "output"))
      (node (ref "R88") (pin "1") (pinfunction "1_1") (pintype "passive"))
      (node (ref "R89") (pin "2") (pinfunction "2_2") (pintype "passive"))
    )
    (net (code "15") (name "/PObuf_25") (class "Default")
      (node (ref "DD10") (pin "6") (pinfunction "3Y_6") (pintype "output"))
      (node (ref "R91") (pin "1") (pinfunction "1_1") (pintype "passive"))
      (node (ref "R92") (pin "2") (pinfunction "2_2") (pintype "passive"))
    )
    (net (code "16") (name "/PObuf_26") (class "Default")
      (node (ref "DD10") (pin "4") (pinfunction "2Y_4") (pintype "output"))
      (node (ref "R94") (pin "1") (pinfunction "1_1") (pintype "passive"))
      (node (ref "R95") (pin "2") (pinfunction "2_2") (pintype "passive"))
    )
    (net (code "17") (name "/PObuf_27") (class "Default")
      (node (ref "DD10") (pin "2") (pinfunction "1Y_2") (pintype "output"))
      (node (ref "R97") (pin "1") (pinfunction "1_1") (pintype "passive"))
      (node (ref "R98") (pin "2") (pinfunction "2_2") (pintype "passive"))
    )
    (net (code "18") (name "/PObuf_28") (class "Default")
      (node (ref "DD10") (pin "8") (pinfunction "4Y_8") (pintype "output"))
      (node (ref "R100") (pin "1") (pinfunction "1_1") (pintype "passive"))
      (node (ref "R101") (pin "2") (pinfunction "2_2") (pintype "passive"))
    )
    (net (code "19") (name "/PObuf_29") (class "Default")
      (node (ref "DD10") (pin "10") (pinfunction "5Y_10") (pintype "output"))
      (node (ref "R103") (pin "1") (pinfunction "1_1") (pintype "passive"))
      (node (ref "R104") (pin "2") (pinfunction "2_2") (pintype "passive"))
    )
    (net (code "20") (name "/PObuf_30") (class "Default")
      (node (ref "DD10") (pin "12") (pinfunction "6Y_12") (pintype "output"))
      (node (ref "R106") (pin "1") (pinfunction "1_1") (pintype "passive"))
      (node (ref "R107") (pin "2") (pinfunction "2_2") (pintype "passive"))
    )
    (net (code "21") (name "/PObuf_31") (class "Default")
      (node (ref "DD8") (pin "2") (pinfunction "1Y_2") (pintype "output"))
      (node (ref "R109") (pin "1") (pinfunction "1_1") (pintype "passive"))
      (node (ref "R110") (pin "2") (pinfunction "2_2") (pintype "passive"))
    )
    (net (code "22") (name "/PObuf_32") (class "Default")
      (node (ref "DD8") (pin "8") (pinfunction "4Y_8") (pintype "output"))
      (node (ref "R112") (pin "1") (pinfunction "1_1") (pintype "passive"))
      (node (ref "R113") (pin "2") (pinfunction "2_2") (pintype "passive"))
    )
    (net (code "23") (name "/Reset") (class "Default")
      (node (ref "DD2") (pin "18") (pinfunction "~{RES}_18") (pintype "input"))
    )
    (net (code "24") (name "/SCK") (class "Default")
      (node (ref "DD2") (pin "12") (pinfunction "SCK_12") (pintype "input"))
    )
    (net (code "25") (name "/cPNP") (class "Default")
      (node (ref "R101") (pin "1") (pinfunction "1_1") (pintype "passive"))
      (node (ref "R104") (pin "1") (pinfunction "1_1") (pintype "passive"))
      (node (ref "R107") (pin "1") (pinfunction "1_1") (pintype "passive"))
      (node (ref "R110") (pin "1") (pinfunction "1_1") (pintype "passive"))
      (node (ref "R113") (pin "1") (pinfunction "1_1") (pintype "passive"))
      (node (ref "R68") (pin "1") (pinfunction "1_1") (pintype "passive"))
      (node (ref "R71") (pin "1") (pinfunction "1_1") (pintype "passive"))
      (node (ref "R74") (pin "1") (pinfunction "1_1") (pintype "passive"))
      (node (ref "R77") (pin "1") (pinfunction "1_1") (pintype "passive"))
      (node (ref "R80") (pin "1") (pinfunction "1_1") (pintype "passive"))
      (node (ref "R83") (pin "1") (pinfunction "1_1") (pintype "passive"))
      (node (ref "R86") (pin "1") (pinfunction "1_1") (pintype "passive"))
      (node (ref "R89") (pin "1") (pinfunction "1_1") (pintype "passive"))
      (node (ref "R92") (pin "1") (pinfunction "1_1") (pintype "passive"))
      (node (ref "R95") (pin "1") (pinfunction "1_1") (pintype "passive"))
      (node (ref "R98") (pin "1") (pinfunction "1_1") (pintype "passive"))
    )
    (net (code "26") (name "/pwrOut_17") (class "Default")
      (node (ref "DD2") (pin "1") (pinfunction "GPB0_1") (pintype "bidirectional"))
      (node (ref "DD8") (pin "13") (pinfunction "6A_13") (pintype "input"))
    )
    (net (code "27") (name "/pwrOut_18") (class "Default")
      (node (ref "DD2") (pin "2") (pinfunction "GPB1_2") (pintype "bidirectional"))
      (node (ref "DD8") (pin "11") (pinfunction "5A_11") (pintype "input"))
    )
    (net (code "28") (name "/pwrOut_19") (class "Default")
      (node (ref "DD2") (pin "3") (pinfunction "GPB2_3") (pintype "bidirectional"))
      (node (ref "DD9") (pin "9") (pinfunction "4A_9") (pintype "input"))
    )
    (net (code "29") (name "/pwrOut_20") (class "Default")
      (node (ref "DD2") (pin "4") (pinfunction "GPB3_4") (pintype "bidirectional"))
      (node (ref "DD9") (pin "11") (pinfunction "5A_11") (pintype "input"))
    )
    (net (code "30") (name "/pwrOut_21") (class "Default")
      (node (ref "DD2") (pin "5") (pinfunction "GPB4_5") (pintype "bidirectional"))
      (node (ref "DD9") (pin "13") (pinfunction "6A_13") (pintype "input"))
    )
    (net (code "31") (name "/pwrOut_22") (class "Default")
      (node (ref "DD2") (pin "6") (pinfunction "GPB5_6") (pintype "bidirectional"))
      (node (ref "DD9") (pin "5") (pinfunction "3A_5") (pintype "input"))
    )
    (net (code "32") (name "/pwrOut_23") (class "Default")
      (node (ref "DD2") (pin "7") (pinfunction "GPB6_7") (pintype "bidirectional"))
      (node (ref "DD9") (pin "3") (pinfunction "2A_3") (pintype "input"))
    )
    (net (code "33") (name "/pwrOut_24") (class "Default")
      (node (ref "DD2") (pin "8") (pinfunction "GPB7_8") (pintype "bidirectional"))
      (node (ref "DD9") (pin "1") (pinfunction "1A_1") (pintype "input"))
    )
    (net (code "34") (name "/pwrOut_25") (class "Default")
      (node (ref "DD10") (pin "5") (pinfunction "3A_5") (pintype "input"))
      (node (ref "DD2") (pin "21") (pinfunction "GPA0_21") (pintype "bidirectional"))
    )
    (net (code "35") (name "/pwrOut_26") (class "Default")
      (node (ref "DD10") (pin "3") (pinfunction "2A_3") (pintype "input"))
      (node (ref "DD2") (pin "22") (pinfunction "GPA1_22") (pintype "bidirectional"))
    )
    (net (code "36") (name "/pwrOut_27") (class "Default")
      (node (ref "DD10") (pin "1") (pinfunction "1A_1") (pintype "input"))
      (node (ref "DD2") (pin "23") (pinfunction "GPA2_23") (pintype "bidirectional"))
    )
    (net (code "37") (name "/pwrOut_28") (class "Default")
      (node (ref "DD10") (pin "9") (pinfunction "4A_9") (pintype "input"))
      (node (ref "DD2") (pin "24") (pinfunction "GPA3_24") (pintype "bidirectional"))
    )
    (net (code "38") (name "/pwrOut_29") (class "Default")
      (node (ref "DD10") (pin "11") (pinfunction "5A_11") (pintype "input"))
      (node (ref "DD2") (pin "25") (pinfunction "GPA4_25") (pintype "bidirectional"))
    )
    (net (code "39") (name "/pwrOut_30") (class "Default")
      (node (ref "DD10") (pin "13") (pinfunction "6A_13") (pintype "input"))
      (node (ref "DD2") (pin "26") (pinfunction "GPA5_26") (pintype "bidirectional"))
    )
    (net (code "40") (name "/pwrOut_31") (class "Default")
      (node (ref "DD2") (pin "27") (pinfunction "GPA6_27") (pintype "bidirectional"))
      (node (ref "DD8") (pin "1") (pinfunction "1A_1") (pintype "input"))
    )
    (net (code "41") (name "/pwrOut_32") (class "Default")
      (node (ref "DD2") (pin "28") (pinfunction "GPA7_28") (pintype "bidirectional"))
      (node (ref "DD8") (pin "9") (pinfunction "4A_9") (pintype "input"))
    )
    (net (code "42") (name "GND") (class "Default")
      (node (ref "C19") (pin "1") (pinfunction "1_1") (pintype "passive"))
      (node (ref "C25") (pin "1") (pinfunction "1_1") (pintype "passive"))
      (node (ref "C26") (pin "1") (pinfunction "1_1") (pintype "passive"))
      (node (ref "C27") (pin "1") (pinfunction "1_1") (pintype "passive"))
      (node (ref "DD10") (pin "7") (pinfunction "GND_7") (pintype "power_in"))
      (node (ref "DD2") (pin "10") (pinfunction "VSS_10") (pintype "power_in"))
      (node (ref "DD8") (pin "7") (pinfunction "GND_7") (pintype "power_in"))
      (node (ref "DD9") (pin "7") (pinfunction "GND_7") (pintype "power_in"))
      (node (ref "R102") (pin "1") (pinfunction "1_1") (pintype "passive"))
      (node (ref "R105") (pin "1") (pinfunction "1_1") (pintype "passive"))
      (node (ref "R108") (pin "1") (pinfunction "1_1") (pintype "passive"))
      (node (ref "R111") (pin "1") (pinfunction "1_1") (pintype "passive"))
      (node (ref "R114") (pin "1") (pinfunction "1_1") (pintype "passive"))
      (node (ref "R65") (pin "1") (pinfunction "1_1") (pintype "passive"))
      (node (ref "R66") (pin "1") (pinfunction "1_1") (pintype "passive"))
      (node (ref "R69") (pin "1") (pinfunction "1_1") (pintype "passive"))
      (node (ref "R72") (pin "1") (pinfunction "1_1") (pintype "passive"))
      (node (ref "R75") (pin "1") (pinfunction "1_1") (pintype "passive"))
      (node (ref "R78") (pin "1") (pinfunction "1_1") (pintype "passive"))
      (node (ref "R81") (pin "1") (pinfunction "1_1") (pintype "passive"))
      (node (ref "R84") (pin "1") (pinfunction "1_1") (pintype "passive"))
      (node (ref "R87") (pin "1") (pinfunction "1_1") (pintype "passive"))
      (node (ref "R90") (pin "1") (pinfunction "1_1") (pintype "passive"))
      (node (ref "R93") (pin "1") (pinfunction "1_1") (pintype "passive"))
      (node (ref "R96") (pin "1") (pinfunction "1_1") (pintype "passive"))
      (node (ref "R99") (pin "1") (pinfunction "1_1") (pintype "passive"))
      (node (ref "VT20") (pin "3") (pinfunction "S_3") (pintype "passive"))
      (node (ref "VT21") (pin "3") (pinfunction "S_3") (pintype "passive"))
      (node (ref "VT22") (pin "3") (pinfunction "S_3") (pintype "passive"))
      (node (ref "VT23") (pin "3") (pinfunction "S_3") (pintype "passive"))
      (node (ref "VT24") (pin "3") (pinfunction "S_3") (pintype "passive"))
      (node (ref "VT25") (pin "3") (pinfunction "S_3") (pintype "passive"))
      (node (ref "VT26") (pin "3") (pinfunction "S_3") (pintype "passive"))
      (node (ref "VT27") (pin "3") (pinfunction "S_3") (pintype "passive"))
      (node (ref "VT28") (pin "3") (pinfunction "S_3") (pintype "passive"))
      (node (ref "VT29") (pin "3") (pinfunction "S_3") (pintype "passive"))
      (node (ref "VT30") (pin "3") (pinfunction "S_3") (pintype "passive"))
      (node (ref "VT31") (pin "3") (pinfunction "S_3") (pintype "passive"))
      (node (ref "VT32") (pin "3") (pinfunction "S_3") (pintype "passive"))
      (node (ref "VT33") (pin "3") (pinfunction "S_3") (pintype "passive"))
      (node (ref "VT34") (pin "3") (pinfunction "S_3") (pintype "passive"))
      (node (ref "VT35") (pin "3") (pinfunction "S_3") (pintype "passive"))
    )
    (net (code "43") (name "Net-(DD2-A0)") (class "Default")
      (node (ref "DD2") (pin "15") (pinfunction "A0_15") (pintype "input"))
      (node (ref "R64") (pin "1") (pinfunction "1_1") (pintype "passive"))
    )
    (net (code "44") (name "Net-(DD2-A1)") (class "Default")
      (node (ref "DD2") (pin "16") (pinfunction "A1_16") (pintype "input"))
      (node (ref "R65") (pin "2") (pinfunction "2_2") (pintype "passive"))
    )
    (net (code "45") (name "Net-(DD2-A2)") (class "Default")
      (node (ref "DD2") (pin "17") (pinfunction "A2_17") (pintype "input"))
      (node (ref "R66") (pin "2") (pinfunction "2_2") (pintype "passive"))
    )
    (net (code "46") (name "Net-(DD8-2A)") (class "Default")
      (node (ref "DD8") (pin "3") (pinfunction "2A_3") (pintype "input"))
      (node (ref "DD8") (pin "5") (pinfunction "3A_5") (pintype "input"))
      (node (ref "R187") (pin "1") (pinfunction "1_1") (pintype "passive"))
    )
    (net (code "47") (name "Net-(VT20-D)") (class "Default")
      (node (ref "VD21") (pin "1") (pinfunction "1_1") (pintype "passive"))
      (node (ref "VT20") (pin "2") (pinfunction "D_2") (pintype "passive"))
      (node (ref "XS3") (pin "1") (pinfunction "1_1") (pintype "passive"))
    )
    (net (code "48") (name "Net-(VT20-G)") (class "Default")
      (node (ref "R67") (pin "2") (pinfunction "2_2") (pintype "passive"))
      (node (ref "R69") (pin "2") (pinfunction "2_2") (pintype "passive"))
      (node (ref "VT20") (pin "1") (pinfunction "G_1") (pintype "passive"))
    )
    (net (code "49") (name "Net-(VT21-D)") (class "Default")
      (node (ref "VD22") (pin "1") (pinfunction "1_1") (pintype "passive"))
      (node (ref "VT21") (pin "2") (pinfunction "D_2") (pintype "passive"))
      (node (ref "XS3") (pin "2") (pinfunction "2_2") (pintype "passive"))
    )
    (net (code "50") (name "Net-(VT21-G)") (class "Default")
      (node (ref "R70") (pin "2") (pinfunction "2_2") (pintype "passive"))
      (node (ref "R72") (pin "2") (pinfunction "2_2") (pintype "passive"))
      (node (ref "VT21") (pin "1") (pinfunction "G_1") (pintype "passive"))
    )
    (net (code "51") (name "Net-(VT22-D)") (class "Default")
      (node (ref "VD23") (pin "1") (pinfunction "1_1") (pintype "passive"))
      (node (ref "VT22") (pin "2") (pinfunction "D_2") (pintype "passive"))
      (node (ref "XS3") (pin "3") (pinfunction "3_3") (pintype "passive"))
    )
    (net (code "52") (name "Net-(VT22-G)") (class "Default")
      (node (ref "R73") (pin "2") (pinfunction "2_2") (pintype "passive"))
      (node (ref "R75") (pin "2") (pinfunction "2_2") (pintype "passive"))
      (node (ref "VT22") (pin "1") (pinfunction "G_1") (pintype "passive"))
    )
    (net (code "53") (name "Net-(VT23-D)") (class "Default")
      (node (ref "VD24") (pin "1") (pinfunction "1_1") (pintype "passive"))
      (node (ref "VT23") (pin "2") (pinfunction "D_2") (pintype "passive"))
      (node (ref "XS3") (pin "4") (pinfunction "4_4") (pintype "passive"))
    )
    (net (code "54") (name "Net-(VT23-G)") (class "Default")
      (node (ref "R76") (pin "2") (pinfunction "2_2") (pintype "passive"))
      (node (ref "R78") (pin "2") (pinfunction "2_2") (pintype "passive"))
      (node (ref "VT23") (pin "1") (pinfunction "G_1") (pintype "passive"))
    )
    (net (code "55") (name "Net-(VT24-D)") (class "Default")
      (node (ref "VD25") (pin "1") (pinfunction "1_1") (pintype "passive"))
      (node (ref "VT24") (pin "2") (pinfunction "D_2") (pintype "passive"))
      (node (ref "XS3") (pin "5") (pinfunction "5_5") (pintype "passive"))
    )
    (net (code "56") (name "Net-(VT24-G)") (class "Default")
      (node (ref "R79") (pin "2") (pinfunction "2_2") (pintype "passive"))
      (node (ref "R81") (pin "2") (pinfunction "2_2") (pintype "passive"))
      (node (ref "VT24") (pin "1") (pinfunction "G_1") (pintype "passive"))
    )
    (net (code "57") (name "Net-(VT25-D)") (class "Default")
      (node (ref "VD26") (pin "1") (pinfunction "1_1") (pintype "passive"))
      (node (ref "VT25") (pin "2") (pinfunction "D_2") (pintype "passive"))
      (node (ref "XS3") (pin "6") (pinfunction "6_6") (pintype "passive"))
    )
    (net (code "58") (name "Net-(VT25-G)") (class "Default")
      (node (ref "R82") (pin "2") (pinfunction "2_2") (pintype "passive"))
      (node (ref "R84") (pin "2") (pinfunction "2_2") (pintype "passive"))
      (node (ref "VT25") (pin "1") (pinfunction "G_1") (pintype "passive"))
    )
    (net (code "59") (name "Net-(VT26-D)") (class "Default")
      (node (ref "VD27") (pin "1") (pinfunction "1_1") (pintype "passive"))
      (node (ref "VT26") (pin "2") (pinfunction "D_2") (pintype "passive"))
      (node (ref "XS3") (pin "7") (pinfunction "7_7") (pintype "passive"))
    )
    (net (code "60") (name "Net-(VT26-G)") (class "Default")
      (node (ref "R85") (pin "2") (pinfunction "2_2") (pintype "passive"))
      (node (ref "R87") (pin "2") (pinfunction "2_2") (pintype "passive"))
      (node (ref "VT26") (pin "1") (pinfunction "G_1") (pintype "passive"))
    )
    (net (code "61") (name "Net-(VT27-D)") (class "Default")
      (node (ref "VD28") (pin "1") (pinfunction "1_1") (pintype "passive"))
      (node (ref "VT27") (pin "2") (pinfunction "D_2") (pintype "passive"))
      (node (ref "XS3") (pin "8") (pinfunction "8_8") (pintype "passive"))
    )
    (net (code "62") (name "Net-(VT27-G)") (class "Default")
      (node (ref "R88") (pin "2") (pinfunction "2_2") (pintype "passive"))
      (node (ref "R90") (pin "2") (pinfunction "2_2") (pintype "passive"))
      (node (ref "VT27") (pin "1") (pinfunction "G_1") (pintype "passive"))
    )
    (net (code "63") (name "Net-(VT28-D)") (class "Default")
      (node (ref "VD29") (pin "1") (pinfunction "1_1") (pintype "passive"))
      (node (ref "VT28") (pin "2") (pinfunction "D_2") (pintype "passive"))
      (node (ref "XS4") (pin "1") (pinfunction "1_1") (pintype "passive"))
    )
    (net (code "64") (name "Net-(VT28-G)") (class "Default")
      (node (ref "R91") (pin "2") (pinfunction "2_2") (pintype "passive"))
      (node (ref "R93") (pin "2") (pinfunction "2_2") (pintype "passive"))
      (node (ref "VT28") (pin "1") (pinfunction "G_1") (pintype "passive"))
    )
    (net (code "65") (name "Net-(VT29-D)") (class "Default")
      (node (ref "VD30") (pin "1") (pinfunction "1_1") (pintype "passive"))
      (node (ref "VT29") (pin "2") (pinfunction "D_2") (pintype "passive"))
      (node (ref "XS4") (pin "2") (pinfunction "2_2") (pintype "passive"))
    )
    (net (code "66") (name "Net-(VT29-G)") (class "Default")
      (node (ref "R94") (pin "2") (pinfunction "2_2") (pintype "passive"))
      (node (ref "R96") (pin "2") (pinfunction "2_2") (pintype "passive"))
      (node (ref "VT29") (pin "1") (pinfunction "G_1") (pintype "passive"))
    )
    (net (code "67") (name "Net-(VT30-D)") (class "Default")
      (node (ref "VD31") (pin "1") (pinfunction "1_1") (pintype "passive"))
      (node (ref "VT30") (pin "2") (pinfunction "D_2") (pintype "passive"))
      (node (ref "XS4") (pin "3") (pinfunction "3_3") (pintype "passive"))
    )
    (net (code "68") (name "Net-(VT30-G)") (class "Default")
      (node (ref "R97") (pin "2") (pinfunction "2_2") (pintype "passive"))
      (node (ref "R99") (pin "2") (pinfunction "2_2") (pintype "passive"))
      (node (ref "VT30") (pin "1") (pinfunction "G_1") (pintype "passive"))
    )
    (net (code "69") (name "Net-(VT31-D)") (class "Default")
      (node (ref "VD32") (pin "1") (pinfunction "1_1") (pintype "passive"))
      (node (ref "VT31") (pin "2") (pinfunction "D_2") (pintype "passive"))
      (node (ref "XS4") (pin "4") (pinfunction "4_4") (pintype "passive"))
    )
    (net (code "70") (name "Net-(VT31-G)") (class "Default")
      (node (ref "R100") (pin "2") (pinfunction "2_2") (pintype "passive"))
      (node (ref "R102") (pin "2") (pinfunction "2_2") (pintype "passive"))
      (node (ref "VT31") (pin "1") (pinfunction "G_1") (pintype "passive"))
    )
    (net (code "71") (name "Net-(VT32-D)") (class "Default")
      (node (ref "VD33") (pin "1") (pinfunction "1_1") (pintype "passive"))
      (node (ref "VT32") (pin "2") (pinfunction "D_2") (pintype "passive"))
      (node (ref "XS4") (pin "5") (pinfunction "5_5") (pintype "passive"))
    )
    (net (code "72") (name "Net-(VT32-G)") (class "Default")
      (node (ref "R103") (pin "2") (pinfunction "2_2") (pintype "passive"))
      (node (ref "R105") (pin "2") (pinfunction "2_2") (pintype "passive"))
      (node (ref "VT32") (pin "1") (pinfunction "G_1") (pintype "passive"))
    )
    (net (code "73") (name "Net-(VT33-D)") (class "Default")
      (node (ref "VD34") (pin "1") (pinfunction "1_1") (pintype "passive"))
      (node (ref "VT33") (pin "2") (pinfunction "D_2") (pintype "passive"))
      (node (ref "XS4") (pin "6") (pinfunction "6_6") (pintype "passive"))
    )
    (net (code "74") (name "Net-(VT33-G)") (class "Default")
      (node (ref "R106") (pin "2") (pinfunction "2_2") (pintype "passive"))
      (node (ref "R108") (pin "2") (pinfunction "2_2") (pintype "passive"))
      (node (ref "VT33") (pin "1") (pinfunction "G_1") (pintype "passive"))
    )
    (net (code "75") (name "Net-(VT34-D)") (class "Default")
      (node (ref "VD35") (pin "1") (pinfunction "1_1") (pintype "passive"))
      (node (ref "VT34") (pin "2") (pinfunction "D_2") (pintype "passive"))
      (node (ref "XS4") (pin "7") (pinfunction "7_7") (pintype "passive"))
    )
    (net (code "76") (name "Net-(VT34-G)") (class "Default")
      (node (ref "R109") (pin "2") (pinfunction "2_2") (pintype "passive"))
      (node (ref "R111") (pin "2") (pinfunction "2_2") (pintype "passive"))
      (node (ref "VT34") (pin "1") (pinfunction "G_1") (pintype "passive"))
    )
    (net (code "77") (name "Net-(VT35-D)") (class "Default")
      (node (ref "VD36") (pin "1") (pinfunction "1_1") (pintype "passive"))
      (node (ref "VT35") (pin "2") (pinfunction "D_2") (pintype "passive"))
      (node (ref "XS4") (pin "8") (pinfunction "8_8") (pintype "passive"))
    )
    (net (code "78") (name "Net-(VT35-G)") (class "Default")
      (node (ref "R112") (pin "2") (pinfunction "2_2") (pintype "passive"))
      (node (ref "R114") (pin "2") (pinfunction "2_2") (pintype "passive"))
      (node (ref "VT35") (pin "1") (pinfunction "G_1") (pintype "passive"))
    )
    (net (code "79") (name "unconnected-(DD2-INTA-Pad20)") (class "Default")
      (node (ref "DD2") (pin "20") (pinfunction "INTA_20") (pintype "output"))
    )
    (net (code "80") (name "unconnected-(DD2-INTB-Pad19)") (class "Default")
      (node (ref "DD2") (pin "19") (pinfunction "INTB_19") (pintype "output"))
    )
    (net (code "81") (name "unconnected-(DD8-2Y-Pad4)") (class "Default")
      (node (ref "DD8") (pin "4") (pinfunction "2Y_4") (pintype "output"))
    )
    (net (code "82") (name "unconnected-(DD8-3Y-Pad6)") (class "Default")
      (node (ref "DD8") (pin "6") (pinfunction "3Y_6") (pintype "output"))
    )
  )
)
